# stm32f103c8_stlink.net
KiCad netlist of a schematic drawn in EAGLE
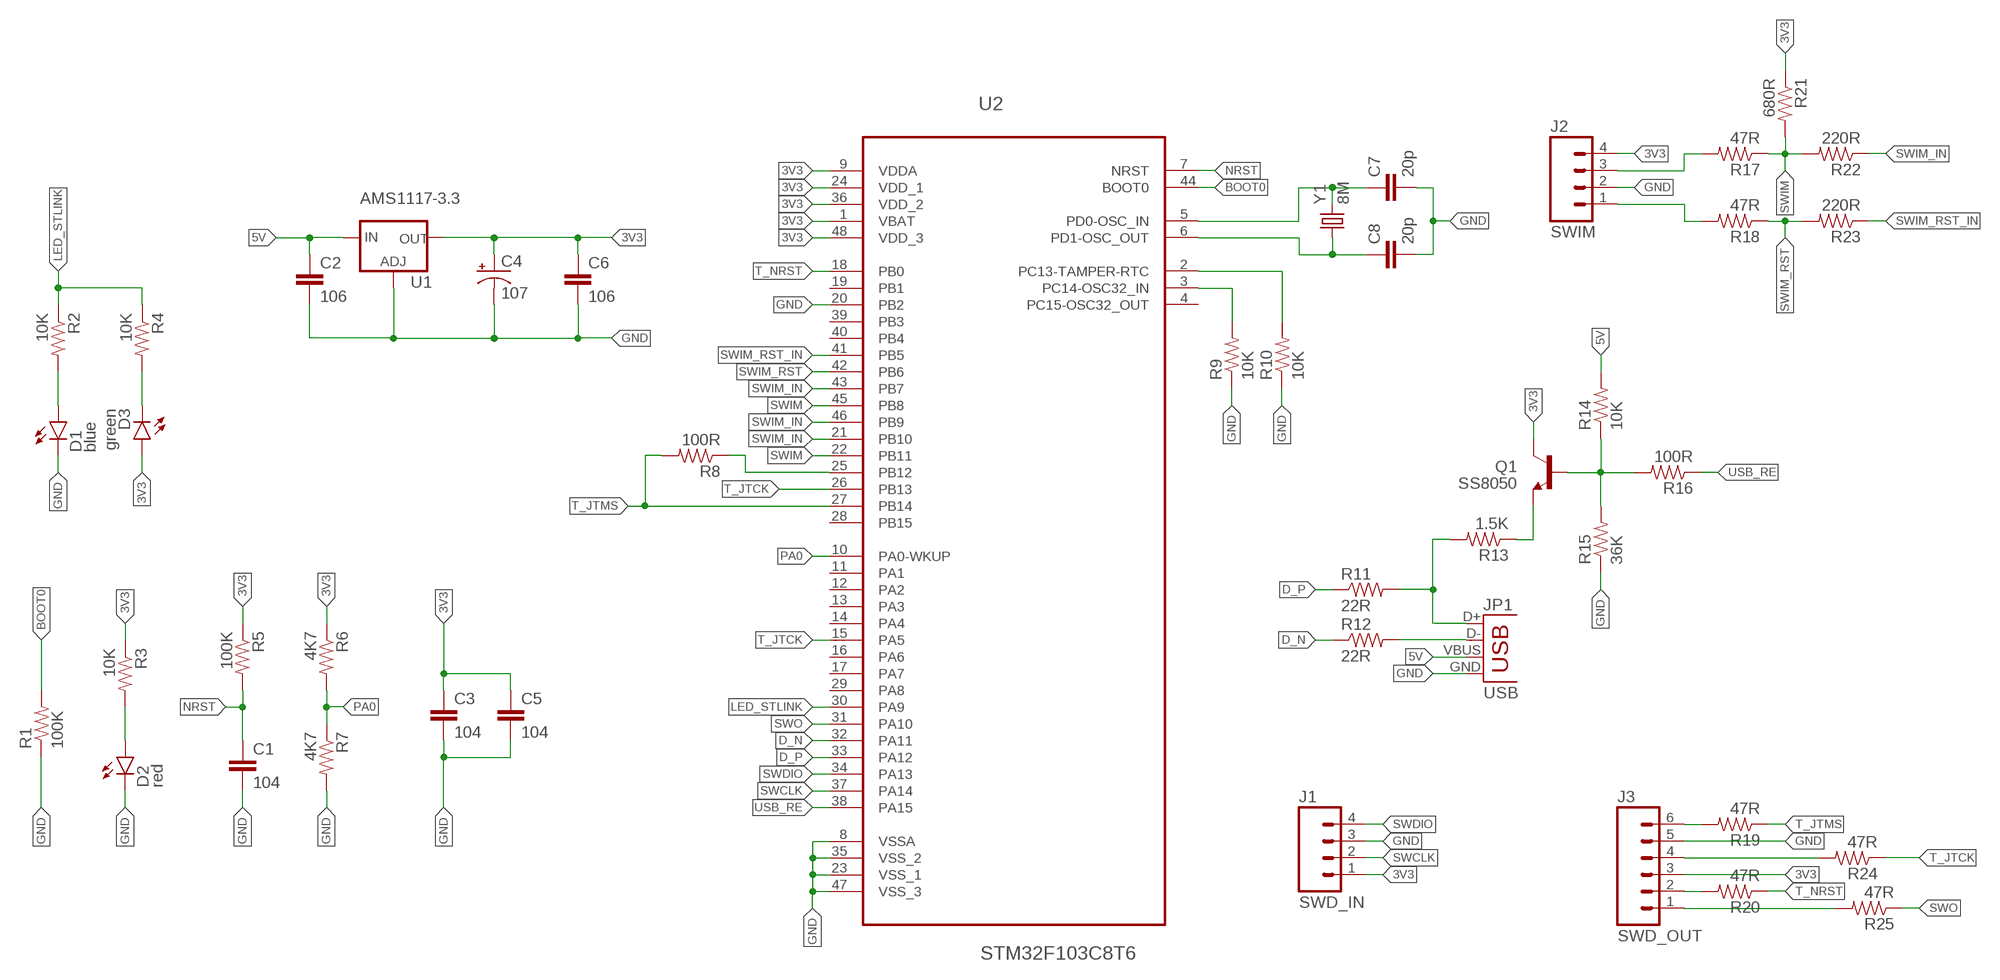
[diagram p0: schematic, sheet 1]

(export (version "E")
  (design (tool "Eeschema 10.0.6"))
  (components
    (comp (ref "C1")
      (value "104")
      (footprint "eagle-import:0603-CAP")
      (libsource (lib "eagle-import") (part "CAP0603-CAP"))
    )
    (comp (ref "C2")
      (value "106")
      (footprint "eagle-import:0603-CAP")
      (libsource (lib "eagle-import") (part "CAP0603-CAP"))
    )
    (comp (ref "C3")
      (value "104")
      (footprint "eagle-import:0603-CAP")
      (libsource (lib "eagle-import") (part "CAP0603-CAP"))
    )
    (comp (ref "C4")
      (value "107")
      (footprint "eagle-import:EIA3528")
      (libsource (lib "eagle-import") (part "CAP_POL3528"))
    )
    (comp (ref "C5")
      (value "104")
      (footprint "eagle-import:0603-CAP")
      (libsource (lib "eagle-import") (part "CAP0603-CAP"))
    )
    (comp (ref "C6")
      (value "106")
      (footprint "eagle-import:0603-CAP")
      (libsource (lib "eagle-import") (part "CAP0603-CAP"))
    )
    (comp (ref "C7")
      (value "20p")
      (footprint "eagle-import:0603-CAP")
      (libsource (lib "eagle-import") (part "CAP0603-CAP"))
    )
    (comp (ref "C8")
      (value "20p")
      (footprint "eagle-import:0603-CAP")
      (libsource (lib "eagle-import") (part "CAP0603-CAP"))
    )
    (comp (ref "D1")
      (value "blue")
      (footprint "eagle-import:LED-0603-SEEED")
      (libsource (lib "eagle-import") (part "LED-SEEED-0603"))
    )
    (comp (ref "D2")
      (value "red")
      (footprint "eagle-import:LED-0603-SEEED")
      (libsource (lib "eagle-import") (part "LED-SEEED-0603"))
    )
    (comp (ref "D3")
      (value "green")
      (footprint "eagle-import:LED-0603-SEEED")
      (libsource (lib "eagle-import") (part "LED-SEEED-0603"))
    )
    (comp (ref "J1")
      (value "SWD_IN")
      (footprint "eagle-import:1X04_NO_SILK")
      (libsource (lib "eagle-import") (part "M041X04_NO_SILK"))
    )
    (comp (ref "J2")
      (value "SWIM")
      (footprint "eagle-import:1X04_NO_SILK")
      (libsource (lib "eagle-import") (part "M041X04_NO_SILK"))
    )
    (comp (ref "J3")
      (value "SWD_OUT")
      (footprint "eagle-import:1X06_NO_SILK")
      (libsource (lib "eagle-import") (part "M06NO_SILK_FEMALE_PTH"))
    )
    (comp (ref "JP1")
      (value "USB")
      (footprint "eagle-import:MICROUSB-U-F-M5DD-Y-1")
      (libsource (lib "eagle-import") (part "USB"))
    )
    (comp (ref "Q1")
      (value "SS8050")
      (footprint "eagle-import:SOT23-3")
      (libsource (lib "eagle-import") (part "TRANSISTOR_NPN-JLC-SMT"))
    )
    (comp (ref "R1")
      (value "100K")
      (footprint "eagle-import:0603-RES")
      (libsource (lib "eagle-import") (part "RESISTOR0603"))
    )
    (comp (ref "R2")
      (value "10K")
      (footprint "eagle-import:0603-RES")
      (libsource (lib "eagle-import") (part "RESISTOR0603"))
    )
    (comp (ref "R3")
      (value "10K")
      (footprint "eagle-import:0603-RES")
      (libsource (lib "eagle-import") (part "RESISTOR0603"))
    )
    (comp (ref "R4")
      (value "10K")
      (footprint "eagle-import:0603-RES")
      (libsource (lib "eagle-import") (part "RESISTOR0603"))
    )
    (comp (ref "R5")
      (value "100K")
      (footprint "eagle-import:0603-RES")
      (libsource (lib "eagle-import") (part "RESISTOR0603"))
    )
    (comp (ref "R6")
      (value "4K7")
      (footprint "eagle-import:0603-RES")
      (libsource (lib "eagle-import") (part "RESISTOR0603"))
    )
    (comp (ref "R7")
      (value "4K7")
      (footprint "eagle-import:0603-RES")
      (libsource (lib "eagle-import") (part "RESISTOR0603"))
    )
    (comp (ref "R8")
      (value "100R")
      (footprint "eagle-import:0603-RES")
      (libsource (lib "eagle-import") (part "RESISTOR0603"))
    )
    (comp (ref "R9")
      (value "10K")
      (footprint "eagle-import:0603-RES")
      (libsource (lib "eagle-import") (part "RESISTOR0603"))
    )
    (comp (ref "R10")
      (value "10K")
      (footprint "eagle-import:0603-RES")
      (libsource (lib "eagle-import") (part "RESISTOR0603"))
    )
    (comp (ref "R11")
      (value "22R")
      (footprint "eagle-import:0603-RES")
      (libsource (lib "eagle-import") (part "RESISTOR0603"))
    )
    (comp (ref "R12")
      (value "22R")
      (footprint "eagle-import:0603-RES")
      (libsource (lib "eagle-import") (part "RESISTOR0603"))
    )
    (comp (ref "R13")
      (value "1.5K")
      (footprint "eagle-import:0603-RES")
      (libsource (lib "eagle-import") (part "RESISTOR0603"))
    )
    (comp (ref "R14")
      (value "10K")
      (footprint "eagle-import:0603-RES")
      (libsource (lib "eagle-import") (part "RESISTOR0603"))
    )
    (comp (ref "R15")
      (value "36K")
      (footprint "eagle-import:0603-RES")
      (libsource (lib "eagle-import") (part "RESISTOR0603"))
    )
    (comp (ref "R16")
      (value "100R")
      (footprint "eagle-import:0603-RES")
      (libsource (lib "eagle-import") (part "RESISTOR0603"))
    )
    (comp (ref "R17")
      (value "47R")
      (footprint "eagle-import:0603-RES")
      (libsource (lib "eagle-import") (part "RESISTOR0603"))
    )
    (comp (ref "R18")
      (value "47R")
      (footprint "eagle-import:0603-RES")
      (libsource (lib "eagle-import") (part "RESISTOR0603"))
    )
    (comp (ref "R19")
      (value "47R")
      (footprint "eagle-import:0603-RES")
      (libsource (lib "eagle-import") (part "RESISTOR0603"))
    )
    (comp (ref "R20")
      (value "47R")
      (footprint "eagle-import:0603-RES")
      (libsource (lib "eagle-import") (part "RESISTOR0603"))
    )
    (comp (ref "R21")
      (value "680R")
      (footprint "eagle-import:0603-RES")
      (libsource (lib "eagle-import") (part "RESISTOR0603"))
    )
    (comp (ref "R22")
      (value "220R")
      (footprint "eagle-import:0603-RES")
      (libsource (lib "eagle-import") (part "RESISTOR0603"))
    )
    (comp (ref "R23")
      (value "220R")
      (footprint "eagle-import:0603-RES")
      (libsource (lib "eagle-import") (part "RESISTOR0603"))
    )
    (comp (ref "R24")
      (value "47R")
      (footprint "eagle-import:0603-RES")
      (libsource (lib "eagle-import") (part "RESISTOR0603"))
    )
    (comp (ref "R25")
      (value "47R")
      (footprint "eagle-import:0603-RES")
      (libsource (lib "eagle-import") (part "RESISTOR0603"))
    )
    (comp (ref "U1")
      (value "AMS1117-3.3")
      (footprint "eagle-import:SOT223")
      (libsource (lib "eagle-import") (part "AMS1117SOT223"))
    )
    (comp (ref "U2")
      (value "STM32F103C8T6")
      (footprint "eagle-import:LQFP-48")
      (fields (field (name "MPN") "STM32F103CBT6"))
      (libsource (lib "eagle-import") (part "STM32F103CBT6"))
    )
    (comp (ref "Y1")
      (value "8M")
      (footprint "eagle-import:HC49US")
      (libsource (lib "eagle-import") (part "CRYSTALHC49US"))
    )
  )
  (nets
    (net (code "1") (name "3V3") (class "Default")
      (node (ref "C3") (pin "1") (pinfunction "1_1") (pintype "passive"))
      (node (ref "C4") (pin "A") (pinfunction "+_A") (pintype "passive"))
      (node (ref "C5") (pin "1") (pinfunction "1_1") (pintype "passive"))
      (node (ref "C6") (pin "1") (pinfunction "1_1") (pintype "passive"))
      (node (ref "D3") (pin "+") (pinfunction "A_+") (pintype "passive"))
      (node (ref "J1") (pin "1") (pinfunction "1_1") (pintype "passive"))
      (node (ref "J2") (pin "4") (pinfunction "4_4") (pintype "passive"))
      (node (ref "J3") (pin "3") (pinfunction "3_3") (pintype "passive"))
      (node (ref "Q1") (pin "3") (pinfunction "C_3") (pintype "passive"))
      (node (ref "R21") (pin "1") (pinfunction "1_1") (pintype "passive"))
      (node (ref "R3") (pin "1") (pinfunction "1_1") (pintype "passive"))
      (node (ref "R5") (pin "1") (pinfunction "1_1") (pintype "passive"))
      (node (ref "R6") (pin "1") (pinfunction "1_1") (pintype "passive"))
      (node (ref "U1") (pin "2") (pinfunction "OUT_2") (pintype "output"))
      (node (ref "U1") (pin "4") (pinfunction "OUT_4") (pintype "output"))
      (node (ref "U2") (pin "1") (pinfunction "VBAT_1") (pintype "input"))
      (node (ref "U2") (pin "24") (pinfunction "VDD_1_24") (pintype "bidirectional"))
      (node (ref "U2") (pin "36") (pinfunction "VDD_2_36") (pintype "power_in"))
      (node (ref "U2") (pin "48") (pinfunction "VDD_3_48") (pintype "power_in"))
      (node (ref "U2") (pin "9") (pinfunction "VDDA_9") (pintype "power_in"))
    )
    (net (code "2") (name "5V") (class "Default")
      (node (ref "C2") (pin "1") (pinfunction "1_1") (pintype "passive"))
      (node (ref "JP1") (pin "VBUS") (pinfunction "VBUS_VBUS") (pintype "bidirectional"))
      (node (ref "R14") (pin "2") (pinfunction "2_2") (pintype "passive"))
      (node (ref "U1") (pin "3") (pinfunction "IN_3") (pintype "input"))
    )
    (net (code "3") (name "BOOT0") (class "Default")
      (node (ref "R1") (pin "2") (pinfunction "2_2") (pintype "passive"))
      (node (ref "U2") (pin "44") (pinfunction "BOOT0_44") (pintype "bidirectional"))
    )
    (net (code "4") (name "D_N") (class "Default")
      (node (ref "R12") (pin "1") (pinfunction "1_1") (pintype "passive"))
      (node (ref "U2") (pin "32") (pinfunction "PA11_32") (pintype "power_in"))
    )
    (net (code "5") (name "D_P") (class "Default")
      (node (ref "R11") (pin "1") (pinfunction "1_1") (pintype "passive"))
      (node (ref "U2") (pin "33") (pinfunction "PA12_33") (pintype "bidirectional"))
    )
    (net (code "6") (name "GND") (class "Default")
      (node (ref "C1") (pin "2") (pinfunction "2_2") (pintype "passive"))
      (node (ref "C2") (pin "2") (pinfunction "2_2") (pintype "passive"))
      (node (ref "C3") (pin "2") (pinfunction "2_2") (pintype "passive"))
      (node (ref "C4") (pin "C") (pinfunction "-_C") (pintype "passive"))
      (node (ref "C5") (pin "2") (pinfunction "2_2") (pintype "passive"))
      (node (ref "C6") (pin "2") (pinfunction "2_2") (pintype "passive"))
      (node (ref "C7") (pin "2") (pinfunction "2_2") (pintype "passive"))
      (node (ref "C8") (pin "2") (pinfunction "2_2") (pintype "passive"))
      (node (ref "D1") (pin "-") (pinfunction "C_-") (pintype "passive"))
      (node (ref "D2") (pin "-") (pinfunction "C_-") (pintype "passive"))
      (node (ref "J1") (pin "3") (pinfunction "3_3") (pintype "passive"))
      (node (ref "J2") (pin "2") (pinfunction "2_2") (pintype "passive"))
      (node (ref "J3") (pin "5") (pinfunction "5_5") (pintype "passive"))
      (node (ref "JP1") (pin "GND") (pinfunction "GND_GND") (pintype "bidirectional"))
      (node (ref "R1") (pin "1") (pinfunction "1_1") (pintype "passive"))
      (node (ref "R10") (pin "1") (pinfunction "1_1") (pintype "passive"))
      (node (ref "R15") (pin "1") (pinfunction "1_1") (pintype "passive"))
      (node (ref "R7") (pin "2") (pinfunction "2_2") (pintype "passive"))
      (node (ref "R9") (pin "1") (pinfunction "1_1") (pintype "passive"))
      (node (ref "U1") (pin "1") (pinfunction "ADJ_1") (pintype "input"))
      (node (ref "U2") (pin "20") (pinfunction "PB2_20") (pintype "bidirectional"))
      (node (ref "U2") (pin "23") (pinfunction "VSS_1_23") (pintype "bidirectional"))
      (node (ref "U2") (pin "35") (pinfunction "VSS_2_35") (pintype "passive"))
      (node (ref "U2") (pin "47") (pinfunction "VSS_3_47") (pintype "passive"))
      (node (ref "U2") (pin "8") (pinfunction "VSSA_8") (pintype "passive"))
    )
    (net (code "7") (name "LED_STLINK") (class "Default")
      (node (ref "R2") (pin "1") (pinfunction "1_1") (pintype "passive"))
      (node (ref "R4") (pin "1") (pinfunction "1_1") (pintype "passive"))
      (node (ref "U2") (pin "30") (pinfunction "PA9_30") (pintype "bidirectional"))
    )
    (net (code "8") (name "NRST") (class "Default")
      (node (ref "C1") (pin "1") (pinfunction "1_1") (pintype "passive"))
      (node (ref "R5") (pin "2") (pinfunction "2_2") (pintype "passive"))
      (node (ref "U2") (pin "7") (pinfunction "NRST_7") (pintype "bidirectional"))
    )
    (net (code "9") (name "Net-(D1-A)") (class "Default")
      (node (ref "D1") (pin "+") (pinfunction "A_+") (pintype "passive"))
      (node (ref "R2") (pin "2") (pinfunction "2_2") (pintype "passive"))
    )
    (net (code "10") (name "Net-(D2-A)") (class "Default")
      (node (ref "D2") (pin "+") (pinfunction "A_+") (pintype "passive"))
      (node (ref "R3") (pin "2") (pinfunction "2_2") (pintype "passive"))
    )
    (net (code "11") (name "Net-(D3-C)") (class "Default")
      (node (ref "D3") (pin "-") (pinfunction "C_-") (pintype "passive"))
      (node (ref "R4") (pin "2") (pinfunction "2_2") (pintype "passive"))
    )
    (net (code "12") (name "Net-(J2-Pad1)") (class "Default")
      (node (ref "J2") (pin "1") (pinfunction "1_1") (pintype "passive"))
      (node (ref "R18") (pin "2") (pinfunction "2_2") (pintype "passive"))
    )
    (net (code "13") (name "Net-(J2-Pad3)") (class "Default")
      (node (ref "J2") (pin "3") (pinfunction "3_3") (pintype "passive"))
      (node (ref "R17") (pin "2") (pinfunction "2_2") (pintype "passive"))
    )
    (net (code "14") (name "Net-(J3-Pad1)") (class "Default")
      (node (ref "J3") (pin "1") (pinfunction "1_1") (pintype "passive"))
      (node (ref "R25") (pin "2") (pinfunction "2_2") (pintype "passive"))
    )
    (net (code "15") (name "Net-(J3-Pad2)") (class "Default")
      (node (ref "J3") (pin "2") (pinfunction "2_2") (pintype "passive"))
      (node (ref "R20") (pin "2") (pinfunction "2_2") (pintype "passive"))
    )
    (net (code "16") (name "Net-(J3-Pad4)") (class "Default")
      (node (ref "J3") (pin "4") (pinfunction "4_4") (pintype "passive"))
      (node (ref "R24") (pin "2") (pinfunction "2_2") (pintype "passive"))
    )
    (net (code "17") (name "Net-(J3-Pad6)") (class "Default")
      (node (ref "J3") (pin "6") (pinfunction "6_6") (pintype "passive"))
      (node (ref "R19") (pin "2") (pinfunction "2_2") (pintype "passive"))
    )
    (net (code "18") (name "Net-(JP1-PadD+)") (class "Default")
      (node (ref "JP1") (pin "D+") (pinfunction "D+_D+") (pintype "bidirectional"))
      (node (ref "R11") (pin "2") (pinfunction "2_2") (pintype "passive"))
      (node (ref "R13") (pin "2") (pinfunction "2_2") (pintype "passive"))
    )
    (net (code "19") (name "Net-(JP1-PadD-)") (class "Default")
      (node (ref "JP1") (pin "D-") (pinfunction "D-_D-") (pintype "bidirectional"))
      (node (ref "R12") (pin "2") (pinfunction "2_2") (pintype "passive"))
    )
    (net (code "20") (name "Net-(Q1-B)") (class "Default")
      (node (ref "Q1") (pin "1") (pinfunction "B_1") (pintype "passive"))
      (node (ref "R14") (pin "1") (pinfunction "1_1") (pintype "passive"))
      (node (ref "R15") (pin "2") (pinfunction "2_2") (pintype "passive"))
      (node (ref "R16") (pin "2") (pinfunction "2_2") (pintype "passive"))
    )
    (net (code "21") (name "Net-(Q1-E)") (class "Default")
      (node (ref "Q1") (pin "2") (pinfunction "E_2") (pintype "passive"))
      (node (ref "R13") (pin "1") (pinfunction "1_1") (pintype "passive"))
    )
    (net (code "22") (name "Net-(U2-PB12)") (class "Default")
      (node (ref "R8") (pin "1") (pinfunction "1_1") (pintype "passive"))
      (node (ref "U2") (pin "25") (pinfunction "PB12_25") (pintype "bidirectional"))
    )
    (net (code "23") (name "Net-(U2-PC13-TAMPER-RTC)") (class "Default")
      (node (ref "R10") (pin "2") (pinfunction "2_2") (pintype "passive"))
      (node (ref "U2") (pin "2") (pinfunction "PC13-TAMPER-RTC_2") (pintype "bidirectional"))
    )
    (net (code "24") (name "Net-(U2-PC14-OSC32_IN)") (class "Default")
      (node (ref "R9") (pin "2") (pinfunction "2_2") (pintype "passive"))
      (node (ref "U2") (pin "3") (pinfunction "PC14-OSC32_IN_3") (pintype "bidirectional"))
    )
    (net (code "25") (name "Net-(U2-PD0-OSC_IN)") (class "Default")
      (node (ref "C7") (pin "1") (pinfunction "1_1") (pintype "passive"))
      (node (ref "U2") (pin "5") (pinfunction "PD0-OSC_IN_5") (pintype "bidirectional"))
      (node (ref "Y1") (pin "2") (pinfunction "2_2") (pintype "passive"))
    )
    (net (code "26") (name "Net-(U2-PD1-OSC_OUT)") (class "Default")
      (node (ref "C8") (pin "1") (pinfunction "1_1") (pintype "passive"))
      (node (ref "U2") (pin "6") (pinfunction "PD1-OSC_OUT_6") (pintype "bidirectional"))
      (node (ref "Y1") (pin "1") (pinfunction "1_1") (pintype "passive"))
    )
    (net (code "27") (name "PA0") (class "Default")
      (node (ref "R6") (pin "2") (pinfunction "2_2") (pintype "passive"))
      (node (ref "R7") (pin "1") (pinfunction "1_1") (pintype "passive"))
      (node (ref "U2") (pin "10") (pinfunction "PA0-WKUP_10") (pintype "bidirectional"))
    )
    (net (code "28") (name "SWCLK") (class "Default")
      (node (ref "J1") (pin "2") (pinfunction "2_2") (pintype "passive"))
      (node (ref "U2") (pin "37") (pinfunction "PA14_37") (pintype "bidirectional"))
    )
    (net (code "29") (name "SWDIO") (class "Default")
      (node (ref "J1") (pin "4") (pinfunction "4_4") (pintype "passive"))
      (node (ref "U2") (pin "34") (pinfunction "PA13_34") (pintype "bidirectional"))
    )
    (net (code "30") (name "SWIM") (class "Default")
      (node (ref "R17") (pin "1") (pinfunction "1_1") (pintype "passive"))
      (node (ref "R21") (pin "2") (pinfunction "2_2") (pintype "passive"))
      (node (ref "R22") (pin "2") (pinfunction "2_2") (pintype "passive"))
      (node (ref "U2") (pin "22") (pinfunction "PB11_22") (pintype "bidirectional"))
      (node (ref "U2") (pin "45") (pinfunction "PB8_45") (pintype "bidirectional"))
    )
    (net (code "31") (name "SWIM_IN") (class "Default")
      (node (ref "R22") (pin "1") (pinfunction "1_1") (pintype "passive"))
      (node (ref "U2") (pin "21") (pinfunction "PB10_21") (pintype "bidirectional"))
      (node (ref "U2") (pin "43") (pinfunction "PB7_43") (pintype "bidirectional"))
      (node (ref "U2") (pin "46") (pinfunction "PB9_46") (pintype "bidirectional"))
    )
    (net (code "32") (name "SWIM_RST") (class "Default")
      (node (ref "R18") (pin "1") (pinfunction "1_1") (pintype "passive"))
      (node (ref "R23") (pin "2") (pinfunction "2_2") (pintype "passive"))
      (node (ref "U2") (pin "42") (pinfunction "PB6_42") (pintype "bidirectional"))
    )
    (net (code "33") (name "SWIM_RST_IN") (class "Default")
      (node (ref "R23") (pin "1") (pinfunction "1_1") (pintype "passive"))
      (node (ref "U2") (pin "41") (pinfunction "PB5_41") (pintype "bidirectional"))
    )
    (net (code "34") (name "SWO") (class "Default")
      (node (ref "R25") (pin "1") (pinfunction "1_1") (pintype "passive"))
      (node (ref "U2") (pin "31") (pinfunction "PA10_31") (pintype "bidirectional"))
    )
    (net (code "35") (name "T_JTCK") (class "Default")
      (node (ref "R24") (pin "1") (pinfunction "1_1") (pintype "passive"))
      (node (ref "U2") (pin "15") (pinfunction "PA5_15") (pintype "bidirectional"))
      (node (ref "U2") (pin "26") (pinfunction "PB13_26") (pintype "bidirectional"))
    )
    (net (code "36") (name "T_JTMS") (class "Default")
      (node (ref "R19") (pin "1") (pinfunction "1_1") (pintype "passive"))
      (node (ref "R8") (pin "2") (pinfunction "2_2") (pintype "passive"))
      (node (ref "U2") (pin "27") (pinfunction "PB14_27") (pintype "bidirectional"))
    )
    (net (code "37") (name "T_NRST") (class "Default")
      (node (ref "R20") (pin "1") (pinfunction "1_1") (pintype "passive"))
      (node (ref "U2") (pin "18") (pinfunction "PB0_18") (pintype "bidirectional"))
    )
    (net (code "38") (name "USB_RE") (class "Default")
      (node (ref "R16") (pin "1") (pinfunction "1_1") (pintype "passive"))
      (node (ref "U2") (pin "38") (pinfunction "PA15_38") (pintype "bidirectional"))
    )
    (net (code "39") (name "unconnected-(U2-PA1-Pad11)") (class "Default")
      (node (ref "U2") (pin "11") (pinfunction "PA1_11") (pintype "bidirectional"))
    )
    (net (code "40") (name "unconnected-(U2-PA2-Pad12)") (class "Default")
      (node (ref "U2") (pin "12") (pinfunction "PA2_12") (pintype "bidirectional"))
    )
    (net (code "41") (name "unconnected-(U2-PA3-Pad13)") (class "Default")
      (node (ref "U2") (pin "13") (pinfunction "PA3_13") (pintype "bidirectional"))
    )
    (net (code "42") (name "unconnected-(U2-PA4-Pad14)") (class "Default")
      (node (ref "U2") (pin "14") (pinfunction "PA4_14") (pintype "bidirectional"))
    )
    (net (code "43") (name "unconnected-(U2-PA6-Pad16)") (class "Default")
      (node (ref "U2") (pin "16") (pinfunction "PA6_16") (pintype "bidirectional"))
    )
    (net (code "44") (name "unconnected-(U2-PA7-Pad17)") (class "Default")
      (node (ref "U2") (pin "17") (pinfunction "PA7_17") (pintype "bidirectional"))
    )
    (net (code "45") (name "unconnected-(U2-PA8-Pad29)") (class "Default")
      (node (ref "U2") (pin "29") (pinfunction "PA8_29") (pintype "bidirectional"))
    )
    (net (code "46") (name "unconnected-(U2-PB1-Pad19)") (class "Default")
      (node (ref "U2") (pin "19") (pinfunction "PB1_19") (pintype "bidirectional"))
    )
    (net (code "47") (name "unconnected-(U2-PB3-Pad39)") (class "Default")
      (node (ref "U2") (pin "39") (pinfunction "PB3_39") (pintype "bidirectional"))
    )
    (net (code "48") (name "unconnected-(U2-PB4-Pad40)") (class "Default")
      (node (ref "U2") (pin "40") (pinfunction "PB4_40") (pintype "bidirectional"))
    )
    (net (code "49") (name "unconnected-(U2-PB15-Pad28)") (class "Default")
      (node (ref "U2") (pin "28") (pinfunction "PB15_28") (pintype "bidirectional"))
    )
    (net (code "50") (name "unconnected-(U2-PC15-OSC32_OUT-Pad4)") (class "Default")
      (node (ref "U2") (pin "4") (pinfunction "PC15-OSC32_OUT_4") (pintype "bidirectional"))
    )
  )
)
